# POWR0011_Regulator_Footprints.net
KiCad netlist of a schematic drawn in Altium Designer
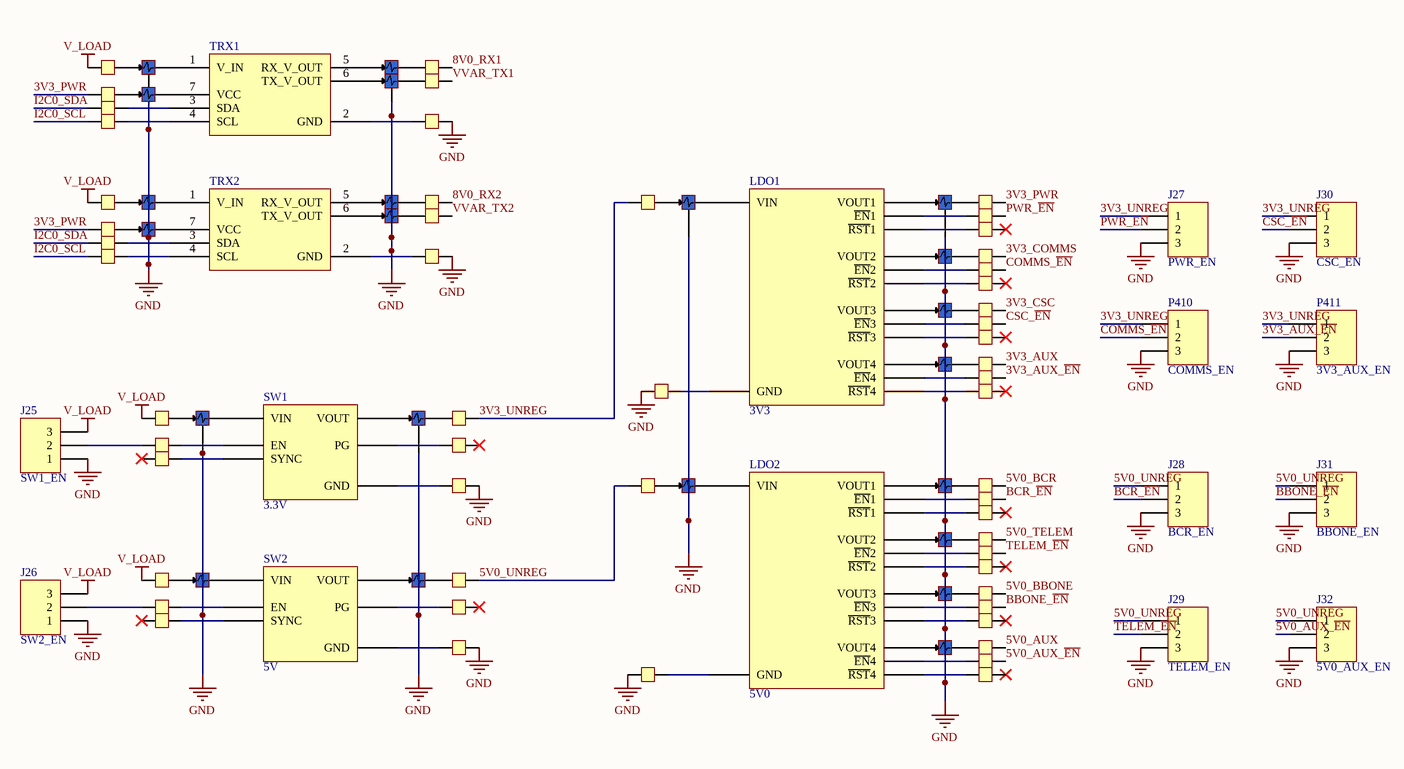
[diagram p0: POWR0011 Regulator Footprints.SchDoc]

(export (version "E")
  (design (tool "Eeschema 10.0.6"))
  (components
    (comp (ref "F106")
      (value "FilterPwr")
      (footprint "FILTERPWR")
      (libsource (lib "FlatBoards") (part "FilterPwr"))
    )
    (comp (ref "F107")
      (value "FilterPwr")
      (footprint "FILTERPWR")
      (libsource (lib "FlatBoards") (part "FilterPwr"))
    )
    (comp (ref "F108")
      (value "FilterPwr")
      (footprint "FILTERPWR")
      (libsource (lib "FlatBoards") (part "FilterPwr"))
    )
    (comp (ref "F109")
      (value "FilterPwr")
      (footprint "FILTERPWR")
      (libsource (lib "FlatBoards") (part "FilterPwr"))
    )
    (comp (ref "F110")
      (value "FilterPwr")
      (footprint "FILTERPWR")
      (libsource (lib "FlatBoards") (part "FilterPwr"))
    )
    (comp (ref "F111")
      (value "FilterPwr")
      (footprint "FILTERPWR")
      (libsource (lib "FlatBoards") (part "FilterPwr"))
    )
    (comp (ref "F112")
      (value "FilterPwr")
      (footprint "FILTERPWR")
      (libsource (lib "FlatBoards") (part "FilterPwr"))
    )
    (comp (ref "F113")
      (value "FilterPwr")
      (footprint "FILTERPWR")
      (libsource (lib "FlatBoards") (part "FilterPwr"))
    )
    (comp (ref "F114")
      (value "FilterPwr")
      (footprint "FILTERPWR")
      (libsource (lib "FlatBoards") (part "FilterPwr"))
    )
    (comp (ref "F115")
      (value "FilterPwr")
      (footprint "FILTERPWR")
      (libsource (lib "FlatBoards") (part "FilterPwr"))
    )
    (comp (ref "F116")
      (value "FilterPwr")
      (footprint "FILTERPWR")
      (libsource (lib "FlatBoards") (part "FilterPwr"))
    )
    (comp (ref "F117")
      (value "FilterPwr")
      (footprint "FILTERPWR")
      (libsource (lib "FlatBoards") (part "FilterPwr"))
    )
    (comp (ref "F118")
      (value "FilterPwr")
      (footprint "FILTERPWR")
      (libsource (lib "FlatBoards") (part "FilterPwr"))
    )
    (comp (ref "F119")
      (value "FilterPwr")
      (footprint "FILTERPWR")
      (libsource (lib "FlatBoards") (part "FilterPwr"))
    )
    (comp (ref "F120")
      (value "FilterPwr")
      (footprint "FILTERPWR")
      (libsource (lib "FlatBoards") (part "FilterPwr"))
    )
    (comp (ref "F121")
      (value "FilterPwr")
      (footprint "FILTERPWR")
      (libsource (lib "FlatBoards") (part "FilterPwr"))
    )
    (comp (ref "F122")
      (value "FilterPwr")
      (footprint "FILTERPWR")
      (libsource (lib "FlatBoards") (part "FilterPwr"))
    )
    (comp (ref "F123")
      (value "FilterPwr")
      (footprint "FILTERPWR")
      (libsource (lib "FlatBoards") (part "FilterPwr"))
    )
    (comp (ref "F124")
      (value "FilterPwr")
      (footprint "FILTERPWR")
      (libsource (lib "FlatBoards") (part "FilterPwr"))
    )
    (comp (ref "F125")
      (value "FilterPwr")
      (footprint "FILTERPWR")
      (libsource (lib "FlatBoards") (part "FilterPwr"))
    )
    (comp (ref "F126")
      (value "FilterPwr")
      (footprint "FILTERPWR")
      (libsource (lib "FlatBoards") (part "FilterPwr"))
    )
    (comp (ref "F127")
      (value "FilterPwr")
      (footprint "FILTERPWR")
      (libsource (lib "FlatBoards") (part "FilterPwr"))
    )
    (comp (ref "J25")
      (value "SW1_EN")
      (footprint "HDR1X3")
      (description "Header, 3-Pin")
      (fields (field (name "PUBLISHER") "Altium Limited"))
      (libsource (lib "") (part "Header 3_1"))
    )
    (comp (ref "J26")
      (value "SW2_EN")
      (footprint "HDR1X3")
      (description "Header, 3-Pin")
      (fields (field (name "PUBLISHER") "Altium Limited"))
      (libsource (lib "") (part "Header 3_1"))
    )
    (comp (ref "J27")
      (value "PWR_EN")
      (footprint "HDR1X3")
      (description "Header, 3-Pin")
      (fields (field (name "PUBLISHER") "Altium Limited"))
      (libsource (lib "Miscellaneous Connectors") (part "Header 3"))
    )
    (comp (ref "J28")
      (value "BCR_EN")
      (footprint "HDR1X3")
      (description "Header, 3-Pin")
      (fields (field (name "PUBLISHER") "Altium Limited"))
      (libsource (lib "Miscellaneous Connectors") (part "Header 3"))
    )
    (comp (ref "J29")
      (value "TELEM_EN")
      (footprint "HDR1X3")
      (description "Header, 3-Pin")
      (fields (field (name "PUBLISHER") "Altium Limited"))
      (libsource (lib "Miscellaneous Connectors") (part "Header 3"))
    )
    (comp (ref "J30")
      (value "CSC_EN")
      (footprint "HDR1X3")
      (description "Header, 3-Pin")
      (fields (field (name "PUBLISHER") "Altium Limited"))
      (libsource (lib "Miscellaneous Connectors") (part "Header 3"))
    )
    (comp (ref "J31")
      (value "BBONE_EN")
      (footprint "HDR1X3")
      (description "Header, 3-Pin")
      (fields (field (name "PUBLISHER") "Altium Limited"))
      (libsource (lib "Miscellaneous Connectors") (part "Header 3"))
    )
    (comp (ref "J32")
      (value "5V0_AUX_EN")
      (footprint "HDR1X3")
      (description "Header, 3-Pin")
      (fields (field (name "PUBLISHER") "Altium Limited"))
      (libsource (lib "Miscellaneous Connectors") (part "Header 3"))
    )
    (comp (ref "LDO1") (value "3V3") (footprint "LDO") (libsource (lib "FlatBoards") (part "LDO")))
    (comp (ref "LDO2") (value "5V0") (footprint "LDO") (libsource (lib "FlatBoards") (part "LDO")))
    (comp (ref "P356") (value "Jumper") (footprint "Jumper") (libsource (lib "FlatBoards") (part "Jumper")))
    (comp (ref "P357") (value "Jumper") (footprint "Jumper") (libsource (lib "") (part "Jumper_1")))
    (comp (ref "P358") (value "Jumper") (footprint "Jumper") (libsource (lib "FlatBoards") (part "Jumper")))
    (comp (ref "P359") (value "Jumper") (footprint "Jumper") (libsource (lib "FlatBoards") (part "Jumper")))
    (comp (ref "P360") (value "Jumper") (footprint "Jumper") (libsource (lib "FlatBoards") (part "Jumper")))
    (comp (ref "P361") (value "Jumper") (footprint "Jumper") (libsource (lib "") (part "Jumper_1")))
    (comp (ref "P362") (value "Jumper") (footprint "Jumper") (libsource (lib "FlatBoards") (part "Jumper")))
    (comp (ref "P363") (value "Jumper") (footprint "Jumper") (libsource (lib "FlatBoards") (part "Jumper")))
    (comp (ref "P364")
      (value "Jumper3")
      (footprint "JUMPER4")
      (libsource (lib "FlatBoards") (part "Jumper3"))
    )
    (comp (ref "P365") (value "Jumper") (footprint "Jumper") (libsource (lib "FlatBoards") (part "Jumper")))
    (comp (ref "P366") (value "Jumper") (footprint "Jumper") (libsource (lib "FlatBoards") (part "Jumper")))
    (comp (ref "P367")
      (value "Jumper3")
      (footprint "JUMPER4")
      (libsource (lib "FlatBoards") (part "Jumper3"))
    )
    (comp (ref "P368") (value "Jumper") (footprint "Jumper") (libsource (lib "FlatBoards") (part "Jumper")))
    (comp (ref "P369") (value "Jumper") (footprint "Jumper") (libsource (lib "FlatBoards") (part "Jumper")))
    (comp (ref "P370") (value "Jumper") (footprint "Jumper") (libsource (lib "FlatBoards") (part "Jumper")))
    (comp (ref "P371") (value "Jumper") (footprint "Jumper") (libsource (lib "FlatBoards") (part "Jumper")))
    (comp (ref "P372") (value "Jumper") (footprint "Jumper") (libsource (lib "FlatBoards") (part "Jumper")))
    (comp (ref "P373") (value "Jumper") (footprint "Jumper") (libsource (lib "FlatBoards") (part "Jumper")))
    (comp (ref "P374") (value "Jumper") (footprint "Jumper") (libsource (lib "FlatBoards") (part "Jumper")))
    (comp (ref "P375") (value "Jumper") (footprint "Jumper") (libsource (lib "FlatBoards") (part "Jumper")))
    (comp (ref "P376")
      (value "Jumper3")
      (footprint "JUMPER4")
      (libsource (lib "FlatBoards") (part "Jumper3"))
    )
    (comp (ref "P377") (value "Jumper") (footprint "Jumper") (libsource (lib "FlatBoards") (part "Jumper")))
    (comp (ref "P378")
      (value "Jumper3")
      (footprint "JUMPER4")
      (libsource (lib "FlatBoards") (part "Jumper3"))
    )
    (comp (ref "P379")
      (value "Jumper3")
      (footprint "JUMPER4")
      (libsource (lib "FlatBoards") (part "Jumper3"))
    )
    (comp (ref "P380") (value "Jumper") (footprint "Jumper") (libsource (lib "FlatBoards") (part "Jumper")))
    (comp (ref "P381")
      (value "Jumper3")
      (footprint "JUMPER4")
      (libsource (lib "FlatBoards") (part "Jumper3"))
    )
    (comp (ref "P382") (value "Jumper") (footprint "Jumper") (libsource (lib "FlatBoards") (part "Jumper")))
    (comp (ref "P383") (value "Jumper") (footprint "Jumper") (libsource (lib "FlatBoards") (part "Jumper")))
    (comp (ref "P384") (value "Jumper") (footprint "Jumper") (libsource (lib "FlatBoards") (part "Jumper")))
    (comp (ref "P385") (value "Jumper") (footprint "Jumper") (libsource (lib "FlatBoards") (part "Jumper")))
    (comp (ref "P386") (value "Jumper") (footprint "Jumper") (libsource (lib "FlatBoards") (part "Jumper")))
    (comp (ref "P387") (value "Jumper") (footprint "Jumper") (libsource (lib "FlatBoards") (part "Jumper")))
    (comp (ref "P388") (value "Jumper") (footprint "Jumper") (libsource (lib "FlatBoards") (part "Jumper")))
    (comp (ref "P389") (value "Jumper") (footprint "Jumper") (libsource (lib "FlatBoards") (part "Jumper")))
    (comp (ref "P390") (value "Jumper") (footprint "Jumper") (libsource (lib "FlatBoards") (part "Jumper")))
    (comp (ref "P391") (value "Jumper") (footprint "Jumper") (libsource (lib "FlatBoards") (part "Jumper")))
    (comp (ref "P392") (value "Jumper") (footprint "Jumper") (libsource (lib "FlatBoards") (part "Jumper")))
    (comp (ref "P393") (value "Jumper") (footprint "Jumper") (libsource (lib "FlatBoards") (part "Jumper")))
    (comp (ref "P394") (value "Jumper") (footprint "Jumper") (libsource (lib "FlatBoards") (part "Jumper")))
    (comp (ref "P395") (value "Jumper") (footprint "Jumper") (libsource (lib "FlatBoards") (part "Jumper")))
    (comp (ref "P396") (value "Jumper") (footprint "Jumper") (libsource (lib "FlatBoards") (part "Jumper")))
    (comp (ref "P397") (value "Jumper") (footprint "Jumper") (libsource (lib "FlatBoards") (part "Jumper")))
    (comp (ref "P398") (value "Jumper") (footprint "Jumper") (libsource (lib "FlatBoards") (part "Jumper")))
    (comp (ref "P399") (value "Jumper") (footprint "Jumper") (libsource (lib "FlatBoards") (part "Jumper")))
    (comp (ref "P400") (value "Jumper") (footprint "Jumper") (libsource (lib "FlatBoards") (part "Jumper")))
    (comp (ref "P401") (value "Jumper") (footprint "Jumper") (libsource (lib "FlatBoards") (part "Jumper")))
    (comp (ref "P402") (value "Jumper") (footprint "Jumper") (libsource (lib "FlatBoards") (part "Jumper")))
    (comp (ref "P403") (value "Jumper") (footprint "Jumper") (libsource (lib "FlatBoards") (part "Jumper")))
    (comp (ref "P404") (value "Jumper") (footprint "Jumper") (libsource (lib "FlatBoards") (part "Jumper")))
    (comp (ref "P405") (value "Jumper") (footprint "Jumper") (libsource (lib "FlatBoards") (part "Jumper")))
    (comp (ref "P406") (value "Jumper") (footprint "Jumper") (libsource (lib "FlatBoards") (part "Jumper")))
    (comp (ref "P407") (value "Jumper") (footprint "Jumper") (libsource (lib "FlatBoards") (part "Jumper")))
    (comp (ref "P408") (value "Jumper") (footprint "Jumper") (libsource (lib "FlatBoards") (part "Jumper")))
    (comp (ref "P409") (value "Jumper") (footprint "Jumper") (libsource (lib "FlatBoards") (part "Jumper")))
    (comp (ref "P410")
      (value "COMMS_EN")
      (footprint "HDR1X3")
      (description "Header, 3-Pin")
      (fields (field (name "PUBLISHER") "Altium Limited"))
      (libsource (lib "Miscellaneous Connectors") (part "Header 3"))
    )
    (comp (ref "P411")
      (value "3V3_AUX_EN")
      (footprint "HDR1X3")
      (description "Header, 3-Pin")
      (fields (field (name "PUBLISHER") "Altium Limited"))
      (libsource (lib "Miscellaneous Connectors") (part "Header 3"))
    )
    (comp (ref "SW1")
      (value "3.3V")
      (footprint "LVSwitcher")
      (libsource (lib "FlatBoards") (part "LVSWITCHER"))
    )
    (comp (ref "SW2")
      (value "5V")
      (footprint "LVSwitcher")
      (libsource (lib "FlatBoards") (part "LVSWITCHER"))
    )
    (comp (ref "TRX1")
      (value "TRX_REGULATOR")
      (footprint "TRX_REGULATOR")
      (libsource (lib "FlatBoards") (part "TRX_REGULATOR"))
    )
    (comp (ref "TRX2")
      (value "TRX_REGULATOR")
      (footprint "TRX_REGULATOR")
      (libsource (lib "FlatBoards") (part "TRX_REGULATOR"))
    )
  )
  (nets
    (net (code "1") (name "/3V3_AUX") (class "Default") (node (ref "P395") (pin "2") (pintype "passive")))
    (net (code "2") (name "/3V3_AUX_~{EN}") (class "Default")
      (node (ref "P396") (pin "2") (pintype "passive"))
      (node (ref "P411") (pin "2") (pinfunction "2_2") (pintype "passive"))
    )
    (net (code "3") (name "/3V3_COMMS") (class "Default") (node (ref "P389") (pin "2") (pintype "passive")))
    (net (code "4") (name "/3V3_CSC") (class "Default") (node (ref "P392") (pin "2") (pintype "passive")))
    (net (code "5") (name "/3V3_PWR") (class "Default")
      (node (ref "P357") (pin "2") (pintype "passive"))
      (node (ref "P361") (pin "2") (pintype "passive"))
      (node (ref "P386") (pin "2") (pintype "passive"))
    )
    (net (code "6") (name "/3V3_UNREG") (class "Default")
      (node (ref "J27") (pin "1") (pinfunction "1_1") (pintype "passive"))
      (node (ref "J30") (pin "1") (pinfunction "1_1") (pintype "passive"))
      (node (ref "P376") (pin "2") (pintype "passive"))
      (node (ref "P382") (pin "1") (pintype "passive"))
      (node (ref "P410") (pin "1") (pinfunction "1_1") (pintype "passive"))
      (node (ref "P411") (pin "1") (pinfunction "1_1") (pintype "passive"))
    )
    (net (code "7") (name "/5V0_AUX") (class "Default") (node (ref "P407") (pin "2") (pintype "passive")))
    (net (code "8") (name "/5V0_AUX_~{EN}") (class "Default")
      (node (ref "J32") (pin "2") (pinfunction "2_2") (pintype "passive"))
      (node (ref "P408") (pin "2") (pintype "passive"))
    )
    (net (code "9") (name "/5V0_BBONE") (class "Default") (node (ref "P404") (pin "2") (pintype "passive")))
    (net (code "10") (name "/5V0_BCR") (class "Default") (node (ref "P398") (pin "2") (pintype "passive")))
    (net (code "11") (name "/5V0_TELEM") (class "Default") (node (ref "P401") (pin "2") (pintype "passive")))
    (net (code "12") (name "/5V0_UNREG") (class "Default")
      (node (ref "J28") (pin "1") (pinfunction "1_1") (pintype "passive"))
      (node (ref "J29") (pin "1") (pinfunction "1_1") (pintype "passive"))
      (node (ref "J31") (pin "1") (pinfunction "1_1") (pintype "passive"))
      (node (ref "J32") (pin "1") (pinfunction "1_1") (pintype "passive"))
      (node (ref "P379") (pin "2") (pintype "passive"))
      (node (ref "P383") (pin "1") (pintype "passive"))
    )
    (net (code "13") (name "/8V0_RX1") (class "Default") (node (ref "P370") (pin "2") (pintype "passive")))
    (net (code "14") (name "/8V0_RX2") (class "Default") (node (ref "P373") (pin "2") (pintype "passive")))
    (net (code "15") (name "/BBONE_~{EN}") (class "Default")
      (node (ref "J31") (pin "2") (pinfunction "2_2") (pintype "passive"))
      (node (ref "P405") (pin "2") (pintype "passive"))
    )
    (net (code "16") (name "/BCR_~{EN}") (class "Default")
      (node (ref "J28") (pin "2") (pinfunction "2_2") (pintype "passive"))
      (node (ref "P399") (pin "2") (pintype "passive"))
    )
    (net (code "17") (name "/COMMS_~{EN}") (class "Default")
      (node (ref "P390") (pin "2") (pintype "passive"))
      (node (ref "P410") (pin "2") (pinfunction "2_2") (pintype "passive"))
    )
    (net (code "18") (name "/CSC_~{EN}") (class "Default")
      (node (ref "J30") (pin "2") (pinfunction "2_2") (pintype "passive"))
      (node (ref "P393") (pin "2") (pintype "passive"))
    )
    (net (code "19") (name "/I2C0_SCL") (class "Default")
      (node (ref "P359") (pin "1") (pintype "passive"))
      (node (ref "P363") (pin "1") (pintype "passive"))
    )
    (net (code "20") (name "/I2C0_SDA") (class "Default")
      (node (ref "P358") (pin "1") (pintype "passive"))
      (node (ref "P362") (pin "1") (pintype "passive"))
    )
    (net (code "21") (name "/PWR_~{EN}") (class "Default")
      (node (ref "J27") (pin "2") (pinfunction "2_2") (pintype "passive"))
      (node (ref "P387") (pin "2") (pintype "passive"))
    )
    (net (code "22") (name "/TELEM_~{EN}") (class "Default")
      (node (ref "J29") (pin "2") (pinfunction "2_2") (pintype "passive"))
      (node (ref "P402") (pin "2") (pintype "passive"))
    )
    (net (code "23") (name "/VVAR_TX1") (class "Default") (node (ref "P371") (pin "2") (pintype "passive")))
    (net (code "24") (name "/VVAR_TX2") (class "Default") (node (ref "P374") (pin "2") (pintype "passive")))
    (net (code "25") (name "GND") (class "Default")
      (node (ref "F106") (pin "3") (pintype "passive"))
      (node (ref "F107") (pin "3") (pintype "passive"))
      (node (ref "F108") (pin "3") (pintype "passive"))
      (node (ref "F109") (pin "3") (pintype "passive"))
      (node (ref "F110") (pin "3") (pintype "passive"))
      (node (ref "F111") (pin "3") (pintype "passive"))
      (node (ref "F112") (pin "3") (pintype "passive"))
      (node (ref "F113") (pin "3") (pintype "passive"))
      (node (ref "F114") (pin "3") (pintype "passive"))
      (node (ref "F115") (pin "3") (pintype "passive"))
      (node (ref "F116") (pin "3") (pintype "passive"))
      (node (ref "F117") (pin "3") (pintype "passive"))
      (node (ref "F118") (pin "3") (pintype "passive"))
      (node (ref "F119") (pin "3") (pintype "passive"))
      (node (ref "F120") (pin "3") (pintype "passive"))
      (node (ref "F121") (pin "3") (pintype "passive"))
      (node (ref "F122") (pin "3") (pintype "passive"))
      (node (ref "F123") (pin "3") (pintype "passive"))
      (node (ref "F124") (pin "3") (pintype "passive"))
      (node (ref "F125") (pin "3") (pintype "passive"))
      (node (ref "F126") (pin "3") (pintype "passive"))
      (node (ref "F127") (pin "3") (pintype "passive"))
      (node (ref "J25") (pin "1") (pinfunction "1_1") (pintype "passive"))
      (node (ref "J26") (pin "1") (pinfunction "1_1") (pintype "passive"))
      (node (ref "J27") (pin "3") (pinfunction "3_3") (pintype "passive"))
      (node (ref "J28") (pin "3") (pinfunction "3_3") (pintype "passive"))
      (node (ref "J29") (pin "3") (pinfunction "3_3") (pintype "passive"))
      (node (ref "J30") (pin "3") (pinfunction "3_3") (pintype "passive"))
      (node (ref "J31") (pin "3") (pinfunction "3_3") (pintype "passive"))
      (node (ref "J32") (pin "3") (pinfunction "3_3") (pintype "passive"))
      (node (ref "P372") (pin "2") (pintype "passive"))
      (node (ref "P375") (pin "2") (pintype "passive"))
      (node (ref "P378") (pin "2") (pintype "passive"))
      (node (ref "P381") (pin "2") (pintype "passive"))
      (node (ref "P384") (pin "1") (pintype "passive"))
      (node (ref "P385") (pin "1") (pintype "passive"))
      (node (ref "P410") (pin "3") (pinfunction "3_3") (pintype "passive"))
      (node (ref "P411") (pin "3") (pinfunction "3_3") (pintype "passive"))
    )
    (net (code "26") (name "Net-(F106-Pad1)") (class "Default")
      (node (ref "F106") (pin "1") (pintype "passive"))
      (node (ref "P356") (pin "2") (pintype "passive"))
    )
    (net (code "27") (name "Net-(F107-Pad1)") (class "Default")
      (node (ref "F107") (pin "1") (pintype "passive"))
      (node (ref "P357") (pin "1") (pintype "passive"))
    )
    (net (code "28") (name "Net-(F108-Pad1)") (class "Default")
      (node (ref "F108") (pin "1") (pintype "passive"))
      (node (ref "P360") (pin "2") (pintype "passive"))
    )
    (net (code "29") (name "Net-(F109-Pad1)") (class "Default")
      (node (ref "F109") (pin "1") (pintype "passive"))
      (node (ref "P361") (pin "1") (pintype "passive"))
    )
    (net (code "30") (name "Net-(F110-Pad1)") (class "Default")
      (node (ref "F110") (pin "1") (pintype "passive"))
      (node (ref "P364") (pin "2") (pintype "passive"))
    )
    (net (code "31") (name "Net-(F111-Pad1)") (class "Default")
      (node (ref "F111") (pin "1") (pintype "passive"))
      (node (ref "P367") (pin "2") (pintype "passive"))
    )
    (net (code "32") (name "Net-(F112-Pad2)") (class "Default")
      (node (ref "F112") (pin "2") (pintype "passive"))
      (node (ref "P370") (pin "1") (pintype "passive"))
    )
    (net (code "33") (name "Net-(F113-Pad2)") (class "Default")
      (node (ref "F113") (pin "2") (pintype "passive"))
      (node (ref "P371") (pin "1") (pintype "passive"))
    )
    (net (code "34") (name "Net-(F114-Pad2)") (class "Default")
      (node (ref "F114") (pin "2") (pintype "passive"))
      (node (ref "P373") (pin "1") (pintype "passive"))
    )
    (net (code "35") (name "Net-(F115-Pad2)") (class "Default")
      (node (ref "F115") (pin "2") (pintype "passive"))
      (node (ref "P374") (pin "1") (pintype "passive"))
    )
    (net (code "36") (name "Net-(F116-Pad2)") (class "Default")
      (node (ref "F116") (pin "2") (pintype "passive"))
      (node (ref "P376") (pin "1") (pintype "passive"))
    )
    (net (code "37") (name "Net-(F117-Pad2)") (class "Default")
      (node (ref "F117") (pin "2") (pintype "passive"))
      (node (ref "P379") (pin "1") (pintype "passive"))
    )
    (net (code "38") (name "Net-(F118-Pad1)") (class "Default")
      (node (ref "F118") (pin "1") (pintype "passive"))
      (node (ref "P382") (pin "2") (pintype "passive"))
    )
    (net (code "39") (name "Net-(F118-Pad2)") (class "Default")
      (node (ref "F118") (pin "2") (pintype "passive"))
      (node (ref "LDO1") (pin "VIN") (pinfunction "VIN_VIN") (pintype "passive"))
    )
    (net (code "40") (name "Net-(F119-Pad1)") (class "Default")
      (node (ref "F119") (pin "1") (pintype "passive"))
      (node (ref "P383") (pin "2") (pintype "passive"))
    )
    (net (code "41") (name "Net-(F119-Pad2)") (class "Default")
      (node (ref "F119") (pin "2") (pintype "passive"))
      (node (ref "LDO2") (pin "VIN") (pinfunction "VIN_VIN") (pintype "passive"))
    )
    (net (code "42") (name "Net-(F120-Pad1)") (class "Default")
      (node (ref "F120") (pin "1") (pintype "passive"))
      (node (ref "LDO1") (pin "VOUT1") (pinfunction "VOUT1_VOUT1") (pintype "passive"))
    )
    (net (code "43") (name "Net-(F120-Pad2)") (class "Default")
      (node (ref "F120") (pin "2") (pintype "passive"))
      (node (ref "P386") (pin "1") (pintype "passive"))
    )
    (net (code "44") (name "Net-(F121-Pad1)") (class "Default")
      (node (ref "F121") (pin "1") (pintype "passive"))
      (node (ref "LDO1") (pin "VOUT2") (pinfunction "VOUT2_VOUT2") (pintype "passive"))
    )
    (net (code "45") (name "Net-(F121-Pad2)") (class "Default")
      (node (ref "F121") (pin "2") (pintype "passive"))
      (node (ref "P389") (pin "1") (pintype "passive"))
    )
    (net (code "46") (name "Net-(F122-Pad1)") (class "Default")
      (node (ref "F122") (pin "1") (pintype "passive"))
      (node (ref "LDO1") (pin "VOUT3") (pinfunction "VOUT3_VOUT3") (pintype "passive"))
    )
    (net (code "47") (name "Net-(F122-Pad2)") (class "Default")
      (node (ref "F122") (pin "2") (pintype "passive"))
      (node (ref "P392") (pin "1") (pintype "passive"))
    )
    (net (code "48") (name "Net-(F123-Pad1)") (class "Default")
      (node (ref "F123") (pin "1") (pintype "passive"))
      (node (ref "LDO1") (pin "VOUT4") (pinfunction "VOUT4_VOUT4") (pintype "passive"))
    )
    (net (code "49") (name "Net-(F123-Pad2)") (class "Default")
      (node (ref "F123") (pin "2") (pintype "passive"))
      (node (ref "P395") (pin "1") (pintype "passive"))
    )
    (net (code "50") (name "Net-(F124-Pad1)") (class "Default")
      (node (ref "F124") (pin "1") (pintype "passive"))
      (node (ref "LDO2") (pin "VOUT1") (pinfunction "VOUT1_VOUT1") (pintype "passive"))
    )
    (net (code "51") (name "Net-(F124-Pad2)") (class "Default")
      (node (ref "F124") (pin "2") (pintype "passive"))
      (node (ref "P398") (pin "1") (pintype "passive"))
    )
    (net (code "52") (name "Net-(F125-Pad1)") (class "Default")
      (node (ref "F125") (pin "1") (pintype "passive"))
      (node (ref "LDO2") (pin "VOUT2") (pinfunction "VOUT2_VOUT2") (pintype "passive"))
    )
    (net (code "53") (name "Net-(F125-Pad2)") (class "Default")
      (node (ref "F125") (pin "2") (pintype "passive"))
      (node (ref "P401") (pin "1") (pintype "passive"))
    )
    (net (code "54") (name "Net-(F126-Pad1)") (class "Default")
      (node (ref "F126") (pin "1") (pintype "passive"))
      (node (ref "LDO2") (pin "VOUT3") (pinfunction "VOUT3_VOUT3") (pintype "passive"))
    )
    (net (code "55") (name "Net-(F126-Pad2)") (class "Default")
      (node (ref "F126") (pin "2") (pintype "passive"))
      (node (ref "P404") (pin "1") (pintype "passive"))
    )
    (net (code "56") (name "Net-(F127-Pad1)") (class "Default")
      (node (ref "F127") (pin "1") (pintype "passive"))
      (node (ref "LDO2") (pin "VOUT4") (pinfunction "VOUT4_VOUT4") (pintype "passive"))
    )
    (net (code "57") (name "Net-(F127-Pad2)") (class "Default")
      (node (ref "F127") (pin "2") (pintype "passive"))
      (node (ref "P407") (pin "1") (pintype "passive"))
    )
    (net (code "58") (name "Net-(J25-Pad2)") (class "Default")
      (node (ref "J25") (pin "2") (pinfunction "2_2") (pintype "passive"))
      (node (ref "P365") (pin "1") (pintype "passive"))
    )
    (net (code "59") (name "Net-(J26-Pad2)") (class "Default")
      (node (ref "J26") (pin "2") (pinfunction "2_2") (pintype "passive"))
      (node (ref "P368") (pin "1") (pintype "passive"))
    )
    (net (code "60") (name "Net-(LDO1-PadGND)") (class "Default")
      (node (ref "LDO1") (pin "GND") (pinfunction "GND_GND") (pintype "passive"))
      (node (ref "P385") (pin "2") (pintype "passive"))
    )
    (net (code "61") (name "Net-(LDO1-~{EN}1)") (class "Default")
      (node (ref "LDO1") (pin "EN1") (pinfunction "~{EN}1_EN1") (pintype "passive"))
      (node (ref "P387") (pin "1") (pintype "passive"))
    )
    (net (code "62") (name "Net-(LDO1-~{EN}2)") (class "Default")
      (node (ref "LDO1") (pin "EN2") (pinfunction "~{EN}2_EN2") (pintype "passive"))
      (node (ref "P390") (pin "1") (pintype "passive"))
    )
    (net (code "63") (name "Net-(LDO1-~{EN}3)") (class "Default")
      (node (ref "LDO1") (pin "EN3") (pinfunction "~{EN}3_EN3") (pintype "passive"))
      (node (ref "P393") (pin "1") (pintype "passive"))
    )
    (net (code "64") (name "Net-(LDO1-~{EN}4)") (class "Default")
      (node (ref "LDO1") (pin "EN4") (pinfunction "~{EN}4_EN4") (pintype "passive"))
      (node (ref "P396") (pin "1") (pintype "passive"))
    )
    (net (code "65") (name "Net-(LDO1-~{RST}1)") (class "Default")
      (node (ref "LDO1") (pin "RST1") (pinfunction "~{RST}1_RST1") (pintype "passive"))
      (node (ref "P388") (pin "1") (pintype "passive"))
    )
    (net (code "66") (name "Net-(LDO1-~{RST}2)") (class "Default")
      (node (ref "LDO1") (pin "RST2") (pinfunction "~{RST}2_RST2") (pintype "passive"))
      (node (ref "P391") (pin "1") (pintype "passive"))
    )
    (net (code "67") (name "Net-(LDO1-~{RST}3)") (class "Default")
      (node (ref "LDO1") (pin "RST3") (pinfunction "~{RST}3_RST3") (pintype "passive"))
      (node (ref "P394") (pin "1") (pintype "passive"))
    )
    (net (code "68") (name "Net-(LDO1-~{RST}4)") (class "Default")
      (node (ref "LDO1") (pin "RST4") (pinfunction "~{RST}4_RST4") (pintype "passive"))
      (node (ref "P397") (pin "1") (pintype "passive"))
    )
    (net (code "69") (name "Net-(LDO2-PadGND)") (class "Default")
      (node (ref "LDO2") (pin "GND") (pinfunction "GND_GND") (pintype "passive"))
      (node (ref "P384") (pin "2") (pintype "passive"))
    )
    (net (code "70") (name "Net-(LDO2-~{EN}1)") (class "Default")
      (node (ref "LDO2") (pin "EN1") (pinfunction "~{EN}1_EN1") (pintype "passive"))
      (node (ref "P399") (pin "1") (pintype "passive"))
    )
    (net (code "71") (name "Net-(LDO2-~{EN}2)") (class "Default")
      (node (ref "LDO2") (pin "EN2") (pinfunction "~{EN}2_EN2") (pintype "passive"))
      (node (ref "P402") (pin "1") (pintype "passive"))
    )
    (net (code "72") (name "Net-(LDO2-~{EN}3)") (class "Default")
      (node (ref "LDO2") (pin "EN3") (pinfunction "~{EN}3_EN3") (pintype "passive"))
      (node (ref "P405") (pin "1") (pintype "passive"))
    )
    (net (code "73") (name "Net-(LDO2-~{EN}4)") (class "Default")
      (node (ref "LDO2") (pin "EN4") (pinfunction "~{EN}4_EN4") (pintype "passive"))
      (node (ref "P408") (pin "1") (pintype "passive"))
    )
    (net (code "74") (name "Net-(LDO2-~{RST}1)") (class "Default")
      (node (ref "LDO2") (pin "RST1") (pinfunction "~{RST}1_RST1") (pintype "passive"))
      (node (ref "P400") (pin "1") (pintype "passive"))
    )
    (net (code "75") (name "Net-(LDO2-~{RST}2)") (class "Default")
      (node (ref "LDO2") (pin "RST2") (pinfunction "~{RST}2_RST2") (pintype "passive"))
      (node (ref "P403") (pin "1") (pintype "passive"))
    )
    (net (code "76") (name "Net-(LDO2-~{RST}3)") (class "Default")
      (node (ref "LDO2") (pin "RST3") (pinfunction "~{RST}3_RST3") (pintype "passive"))
      (node (ref "P406") (pin "1") (pintype "passive"))
    )
    (net (code "77") (name "Net-(LDO2-~{RST}4)") (class "Default")
      (node (ref "LDO2") (pin "RST4") (pinfunction "~{RST}4_RST4") (pintype "passive"))
      (node (ref "P409") (pin "1") (pintype "passive"))
    )
    (net (code "78") (name "Net-(P365-Pad2)") (class "Default")
      (node (ref "P365") (pin "2") (pintype "passive"))
      (node (ref "SW1") (pin "EN") (pinfunction "EN_EN") (pintype "passive"))
    )
    (net (code "79") (name "Net-(P366-Pad2)") (class "Default")
      (node (ref "P366") (pin "2") (pintype "passive"))
      (node (ref "SW1") (pin "SYNC") (pinfunction "SYNC_SYNC") (pintype "passive"))
    )
    (net (code "80") (name "Net-(P368-Pad2)") (class "Default")
      (node (ref "P368") (pin "2") (pintype "passive"))
      (node (ref "SW2") (pin "EN") (pinfunction "EN_EN") (pintype "passive"))
    )
    (net (code "81") (name "Net-(P369-Pad2)") (class "Default")
      (node (ref "P369") (pin "2") (pintype "passive"))
      (node (ref "SW2") (pin "SYNC") (pinfunction "SYNC_SYNC") (pintype "passive"))
    )
    (net (code "82") (name "Net-(P377-Pad1)") (class "Default")
      (node (ref "P377") (pin "1") (pintype "passive"))
      (node (ref "SW1") (pin "PG") (pinfunction "PG_PG") (pintype "passive"))
    )
    (net (code "83") (name "Net-(P378-Pad1)") (class "Default")
      (node (ref "P378") (pin "1") (pintype "passive"))
      (node (ref "SW1") (pin "GND") (pinfunction "GND_GND") (pintype "passive"))
    )
    (net (code "84") (name "Net-(P380-Pad1)") (class "Default")
      (node (ref "P380") (pin "1") (pintype "passive"))
      (node (ref "SW2") (pin "PG") (pinfunction "PG_PG") (pintype "passive"))
    )
    (net (code "85") (name "Net-(P381-Pad1)") (class "Default")
      (node (ref "P381") (pin "1") (pintype "passive"))
      (node (ref "SW2") (pin "GND") (pinfunction "GND_GND") (pintype "passive"))
    )
    (net (code "86") (name "Net-(SW1-VIN)") (class "Default")
      (node (ref "F110") (pin "2") (pintype "passive"))
      (node (ref "SW1") (pin "Vin") (pinfunction "VIN_Vin") (pintype "passive"))
    )
    (net (code "87") (name "Net-(SW1-VOUT)") (class "Default")
      (node (ref "F116") (pin "1") (pintype "passive"))
      (node (ref "SW1") (pin "Vout") (pinfunction "VOUT_Vout") (pintype "passive"))
    )
    (net (code "88") (name "Net-(SW2-VIN)") (class "Default")
      (node (ref "F111") (pin "2") (pintype "passive"))
      (node (ref "SW2") (pin "Vin") (pinfunction "VIN_Vin") (pintype "passive"))
    )
    (net (code "89") (name "Net-(SW2-VOUT)") (class "Default")
      (node (ref "F117") (pin "1") (pintype "passive"))
      (node (ref "SW2") (pin "Vout") (pinfunction "VOUT_Vout") (pintype "passive"))
    )
    (net (code "90") (name "Net-(TRX1-GND)") (class "Default")
      (node (ref "P372") (pin "1") (pintype "passive"))
      (node (ref "TRX1") (pin "2") (pinfunction "GND_2") (pintype "passive"))
    )
    (net (code "91") (name "Net-(TRX1-RX_V_OUT)") (class "Default")
      (node (ref "F112") (pin "1") (pintype "passive"))
      (node (ref "TRX1") (pin "5") (pinfunction "RX_V_OUT_5") (pintype "passive"))
    )
    (net (code "92") (name "Net-(TRX1-SCL)") (class "Default")
      (node (ref "P359") (pin "2") (pintype "passive"))
      (node (ref "TRX1") (pin "4") (pinfunction "SCL_4") (pintype "passive"))
    )
    (net (code "93") (name "Net-(TRX1-SDA)") (class "Default")
      (node (ref "P358") (pin "2") (pintype "passive"))
      (node (ref "TRX1") (pin "3") (pinfunction "SDA_3") (pintype "passive"))
    )
    (net (code "94") (name "Net-(TRX1-TX_V_OUT)") (class "Default")
      (node (ref "F113") (pin "1") (pintype "passive"))
      (node (ref "TRX1") (pin "6") (pinfunction "TX_V_OUT_6") (pintype "passive"))
    )
    (net (code "95") (name "Net-(TRX1-VCC)") (class "Default")
      (node (ref "F107") (pin "2") (pintype "passive"))
      (node (ref "TRX1") (pin "7") (pinfunction "VCC_7") (pintype "passive"))
    )
    (net (code "96") (name "Net-(TRX1-V_IN)") (class "Default")
      (node (ref "F106") (pin "2") (pintype "passive"))
      (node (ref "TRX1") (pin "1") (pinfunction "V_IN_1") (pintype "passive"))
    )
    (net (code "97") (name "Net-(TRX2-GND)") (class "Default")
      (node (ref "P375") (pin "1") (pintype "passive"))
      (node (ref "TRX2") (pin "2") (pinfunction "GND_2") (pintype "passive"))
    )
    (net (code "98") (name "Net-(TRX2-RX_V_OUT)") (class "Default")
      (node (ref "F114") (pin "1") (pintype "passive"))
      (node (ref "TRX2") (pin "5") (pinfunction "RX_V_OUT_5") (pintype "passive"))
    )
    (net (code "99") (name "Net-(TRX2-SCL)") (class "Default")
      (node (ref "P363") (pin "2") (pintype "passive"))
      (node (ref "TRX2") (pin "4") (pinfunction "SCL_4") (pintype "passive"))
    )
    (net (code "100") (name "Net-(TRX2-SDA)") (class "Default")
      (node (ref "P362") (pin "2") (pintype "passive"))
      (node (ref "TRX2") (pin "3") (pinfunction "SDA_3") (pintype "passive"))
    )
    (net (code "101") (name "Net-(TRX2-TX_V_OUT)") (class "Default")
      (node (ref "F115") (pin "1") (pintype "passive"))
      (node (ref "TRX2") (pin "6") (pinfunction "TX_V_OUT_6") (pintype "passive"))
    )
    (net (code "102") (name "Net-(TRX2-VCC)") (class "Default")
      (node (ref "F109") (pin "2") (pintype "passive"))
      (node (ref "TRX2") (pin "7") (pinfunction "VCC_7") (pintype "passive"))
    )
    (net (code "103") (name "Net-(TRX2-V_IN)") (class "Default")
      (node (ref "F108") (pin "2") (pintype "passive"))
      (node (ref "TRX2") (pin "1") (pinfunction "V_IN_1") (pintype "passive"))
    )
    (net (code "104") (name "V_LOAD") (class "Default")
      (node (ref "J25") (pin "3") (pinfunction "3_3") (pintype "passive"))
      (node (ref "J26") (pin "3") (pinfunction "3_3") (pintype "passive"))
      (node (ref "P356") (pin "1") (pintype "passive"))
      (node (ref "P360") (pin "1") (pintype "passive"))
      (node (ref "P364") (pin "1") (pintype "passive"))
      (node (ref "P367") (pin "1") (pintype "passive"))
    )
    (net (code "105") (name "unconnected-(P366-Pad1)") (class "Default")
      (node (ref "P366") (pin "1") (pintype "passive+no_connect"))
    )
    (net (code "106") (name "unconnected-(P369-Pad1)") (class "Default")
      (node (ref "P369") (pin "1") (pintype "passive+no_connect"))
    )
    (net (code "107") (name "unconnected-(P377-Pad2)") (class "Default")
      (node (ref "P377") (pin "2") (pintype "passive+no_connect"))
    )
    (net (code "108") (name "unconnected-(P380-Pad2)") (class "Default")
      (node (ref "P380") (pin "2") (pintype "passive+no_connect"))
    )
    (net (code "109") (name "unconnected-(P388-Pad2)") (class "Default")
      (node (ref "P388") (pin "2") (pintype "passive+no_connect"))
    )
    (net (code "110") (name "unconnected-(P391-Pad2)") (class "Default")
      (node (ref "P391") (pin "2") (pintype "passive+no_connect"))
    )
    (net (code "111") (name "unconnected-(P394-Pad2)") (class "Default")
      (node (ref "P394") (pin "2") (pintype "passive+no_connect"))
    )
    (net (code "112") (name "unconnected-(P397-Pad2)") (class "Default")
      (node (ref "P397") (pin "2") (pintype "passive+no_connect"))
    )
    (net (code "113") (name "unconnected-(P400-Pad2)") (class "Default")
      (node (ref "P400") (pin "2") (pintype "passive+no_connect"))
    )
    (net (code "114") (name "unconnected-(P403-Pad2)") (class "Default")
      (node (ref "P403") (pin "2") (pintype "passive+no_connect"))
    )
    (net (code "115") (name "unconnected-(P406-Pad2)") (class "Default")
      (node (ref "P406") (pin "2") (pintype "passive+no_connect"))
    )
    (net (code "116") (name "unconnected-(P409-Pad2)") (class "Default")
      (node (ref "P409") (pin "2") (pintype "passive+no_connect"))
    )
  )
)
